# InputLevelShifter.net
KiCad netlist of a schematic drawn in Altium Designer
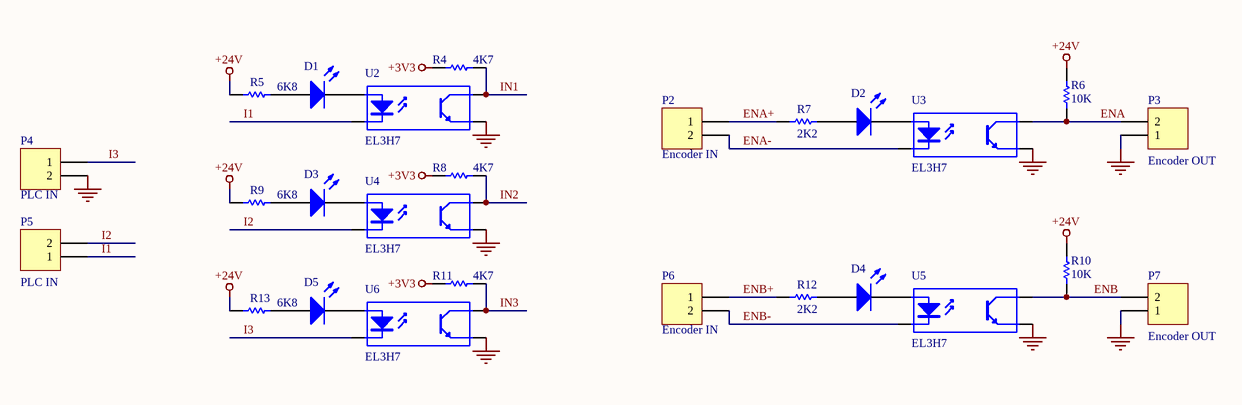
[diagram p0: InputLevelShifter.SchDoc]

(export (version "E")
  (design (tool "Eeschema 10.0.6"))
  (components
    (comp (ref "D1")
      (value "SMD0805-RED")
      (footprint "LED-0805")
      (description "Typical INFRARED GaAs LED")
      (libsource (lib "Miscellaneous Devices") (part "LED0"))
    )
    (comp (ref "D2")
      (value "SMD0805-RED")
      (footprint "LED-0805")
      (description "Typical INFRARED GaAs LED")
      (libsource (lib "Miscellaneous Devices") (part "LED0"))
    )
    (comp (ref "D3")
      (value "SMD0805-RED")
      (footprint "LED-0805")
      (description "Typical INFRARED GaAs LED")
      (libsource (lib "Miscellaneous Devices") (part "LED0"))
    )
    (comp (ref "D4")
      (value "SMD0805-RED")
      (footprint "LED-0805")
      (description "Typical INFRARED GaAs LED")
      (libsource (lib "Miscellaneous Devices") (part "LED0"))
    )
    (comp (ref "D5")
      (value "SMD0805-RED")
      (footprint "LED-0805")
      (description "Typical INFRARED GaAs LED")
      (libsource (lib "Miscellaneous Devices") (part "LED0"))
    )
    (comp (ref "P2")
      (value "Encoder IN")
      (footprint "TER-KF128-2P")
      (description "Header, 2-Pin")
      (fields (field (name "Comment") "KF128-2P"))
      (libsource (lib "") (part "Header 2_1"))
    )
    (comp (ref "P3")
      (value "Encoder OUT")
      (footprint "TER-KF128-2P")
      (description "Header, 2-Pin")
      (fields (field (name "Comment") "KF128-2P"))
      (libsource (lib "Miscellaneous Connectors") (part "Header 2"))
    )
    (comp (ref "P4")
      (value "PLC IN")
      (footprint "TER-KF128-2P")
      (description "Header, 2-Pin")
      (fields (field (name "Comment") "KF128-2P"))
      (libsource (lib "") (part "Header 2_1"))
    )
    (comp (ref "P5")
      (value "PLC IN")
      (footprint "TER-KF128-2P")
      (description "Header, 2-Pin")
      (fields (field (name "Comment") "KF128-2P"))
      (libsource (lib "") (part "Header 2_2"))
    )
    (comp (ref "P6")
      (value "Encoder IN")
      (footprint "TER-KF128-2P")
      (description "Header, 2-Pin")
      (fields (field (name "Comment") "KF128-2P"))
      (libsource (lib "") (part "Header 2_1"))
    )
    (comp (ref "P7")
      (value "Encoder OUT")
      (footprint "TER-KF128-2P")
      (description "Header, 2-Pin")
      (fields (field (name "Comment") "KF128-2P"))
      (libsource (lib "Miscellaneous Connectors") (part "Header 2"))
    )
    (comp (ref "R4")
      (value "4K7")
      (footprint "R-0805")
      (description "Resistor")
      (fields (field (name "PUBLISHER") "Altium Limited"))
      (libsource (lib "Miscellaneous Devices") (part "Res1"))
    )
    (comp (ref "R5")
      (value "6K8")
      (footprint "R-0805")
      (description "Resistor")
      (fields (field (name "PUBLISHER") "Altium Limited"))
      (libsource (lib "Miscellaneous Devices") (part "Res1"))
    )
    (comp (ref "R6")
      (value "10K")
      (footprint "R-0805")
      (description "Resistor")
      (fields (field (name "PUBLISHER") "Altium Limited"))
      (libsource (lib "Miscellaneous Devices") (part "Res1"))
    )
    (comp (ref "R7")
      (value "2K2")
      (footprint "R-0805")
      (description "Resistor")
      (fields (field (name "PUBLISHER") "Altium Limited"))
      (libsource (lib "Miscellaneous Devices") (part "Res1"))
    )
    (comp (ref "R8")
      (value "4K7")
      (footprint "R-0805")
      (description "Resistor")
      (fields (field (name "PUBLISHER") "Altium Limited"))
      (libsource (lib "Miscellaneous Devices") (part "Res1"))
    )
    (comp (ref "R9")
      (value "6K8")
      (footprint "R-0805")
      (description "Resistor")
      (fields (field (name "PUBLISHER") "Altium Limited"))
      (libsource (lib "Miscellaneous Devices") (part "Res1"))
    )
    (comp (ref "R10")
      (value "10K")
      (footprint "R-0805")
      (description "Resistor")
      (fields (field (name "PUBLISHER") "Altium Limited"))
      (libsource (lib "Miscellaneous Devices") (part "Res1"))
    )
    (comp (ref "R11")
      (value "4K7")
      (footprint "R-0805")
      (description "Resistor")
      (fields (field (name "PUBLISHER") "Altium Limited"))
      (libsource (lib "Miscellaneous Devices") (part "Res1"))
    )
    (comp (ref "R12")
      (value "2K2")
      (footprint "R-0805")
      (description "Resistor")
      (fields (field (name "PUBLISHER") "Altium Limited"))
      (libsource (lib "Miscellaneous Devices") (part "Res1"))
    )
    (comp (ref "R13")
      (value "6K8")
      (footprint "R-0805")
      (description "Resistor")
      (fields (field (name "PUBLISHER") "Altium Limited"))
      (libsource (lib "Miscellaneous Devices") (part "Res1"))
    )
    (comp (ref "U2")
      (value "EL3H7")
      (footprint "SSOP-4")
      (description "4-Pin Phototransistor Optocoupler")
      (libsource (lib "Miscellaneous Devices") (part "Optoisolator1"))
    )
    (comp (ref "U3")
      (value "EL3H7")
      (footprint "SSOP-4")
      (description "4-Pin Phototransistor Optocoupler")
      (libsource (lib "Miscellaneous Devices") (part "Optoisolator1"))
    )
    (comp (ref "U4")
      (value "EL3H7")
      (footprint "SSOP-4")
      (description "4-Pin Phototransistor Optocoupler")
      (libsource (lib "Miscellaneous Devices") (part "Optoisolator1"))
    )
    (comp (ref "U5")
      (value "EL3H7")
      (footprint "SSOP-4")
      (description "4-Pin Phototransistor Optocoupler")
      (libsource (lib "Miscellaneous Devices") (part "Optoisolator1"))
    )
    (comp (ref "U6")
      (value "EL3H7")
      (footprint "SSOP-4")
      (description "4-Pin Phototransistor Optocoupler")
      (libsource (lib "Miscellaneous Devices") (part "Optoisolator1"))
    )
  )
  (nets
    (net (code "1") (name "+3V3") (class "Default")
      (node (ref "R11") (pin "2") (pinfunction "2_2") (pintype "passive"))
      (node (ref "R4") (pin "2") (pinfunction "2_2") (pintype "passive"))
      (node (ref "R8") (pin "2") (pinfunction "2_2") (pintype "passive"))
    )
    (net (code "2") (name "+24V") (class "Default")
      (node (ref "R10") (pin "2") (pinfunction "2_2") (pintype "passive"))
      (node (ref "R13") (pin "1") (pinfunction "1_1") (pintype "passive"))
      (node (ref "R5") (pin "1") (pinfunction "1_1") (pintype "passive"))
      (node (ref "R6") (pin "2") (pinfunction "2_2") (pintype "passive"))
      (node (ref "R9") (pin "1") (pinfunction "1_1") (pintype "passive"))
    )
    (net (code "3") (name "/ENA") (class "Default")
      (node (ref "P3") (pin "2") (pinfunction "2_2") (pintype "passive"))
      (node (ref "R6") (pin "1") (pinfunction "1_1") (pintype "passive"))
      (node (ref "U3") (pin "4") (pinfunction "C_4") (pintype "passive"))
    )
    (net (code "4") (name "/ENA+") (class "Default")
      (node (ref "P2") (pin "1") (pinfunction "1_1") (pintype "passive"))
      (node (ref "R7") (pin "1") (pinfunction "1_1") (pintype "passive"))
    )
    (net (code "5") (name "/ENA-") (class "Default")
      (node (ref "P2") (pin "2") (pinfunction "2_2") (pintype "passive"))
      (node (ref "U3") (pin "2") (pinfunction "K_2") (pintype "passive"))
    )
    (net (code "6") (name "/ENB") (class "Default")
      (node (ref "P7") (pin "2") (pinfunction "2_2") (pintype "passive"))
      (node (ref "R10") (pin "1") (pinfunction "1_1") (pintype "passive"))
      (node (ref "U5") (pin "4") (pinfunction "C_4") (pintype "passive"))
    )
    (net (code "7") (name "/ENB+") (class "Default")
      (node (ref "P6") (pin "1") (pinfunction "1_1") (pintype "passive"))
      (node (ref "R12") (pin "1") (pinfunction "1_1") (pintype "passive"))
    )
    (net (code "8") (name "/ENB-") (class "Default")
      (node (ref "P6") (pin "2") (pinfunction "2_2") (pintype "passive"))
      (node (ref "U5") (pin "2") (pinfunction "K_2") (pintype "passive"))
    )
    (net (code "9") (name "/I1") (class "Default")
      (node (ref "P5") (pin "1") (pinfunction "1_1") (pintype "passive"))
      (node (ref "U2") (pin "2") (pinfunction "K_2") (pintype "passive"))
    )
    (net (code "10") (name "/I2") (class "Default")
      (node (ref "P5") (pin "2") (pinfunction "2_2") (pintype "passive"))
      (node (ref "U4") (pin "2") (pinfunction "K_2") (pintype "passive"))
    )
    (net (code "11") (name "/I3") (class "Default")
      (node (ref "P4") (pin "1") (pinfunction "1_1") (pintype "passive"))
      (node (ref "U6") (pin "2") (pinfunction "K_2") (pintype "passive"))
    )
    (net (code "12") (name "/IN1") (class "Default")
      (node (ref "R4") (pin "1") (pinfunction "1_1") (pintype "passive"))
      (node (ref "U2") (pin "4") (pinfunction "C_4") (pintype "passive"))
    )
    (net (code "13") (name "/IN2") (class "Default")
      (node (ref "R8") (pin "1") (pinfunction "1_1") (pintype "passive"))
      (node (ref "U4") (pin "4") (pinfunction "C_4") (pintype "passive"))
    )
    (net (code "14") (name "/IN3") (class "Default")
      (node (ref "R11") (pin "1") (pinfunction "1_1") (pintype "passive"))
      (node (ref "U6") (pin "4") (pinfunction "C_4") (pintype "passive"))
    )
    (net (code "15") (name "GND") (class "Default")
      (node (ref "P3") (pin "1") (pinfunction "1_1") (pintype "passive"))
      (node (ref "P4") (pin "2") (pinfunction "2_2") (pintype "passive"))
      (node (ref "P7") (pin "1") (pinfunction "1_1") (pintype "passive"))
      (node (ref "U2") (pin "3") (pinfunction "E_3") (pintype "passive"))
      (node (ref "U3") (pin "3") (pinfunction "E_3") (pintype "passive"))
      (node (ref "U4") (pin "3") (pinfunction "E_3") (pintype "passive"))
      (node (ref "U5") (pin "3") (pinfunction "E_3") (pintype "passive"))
      (node (ref "U6") (pin "3") (pinfunction "E_3") (pintype "passive"))
    )
    (net (code "16") (name "Net-(D1-A)") (class "Default")
      (node (ref "D1") (pin "1") (pinfunction "A_1") (pintype "passive"))
      (node (ref "R5") (pin "2") (pinfunction "2_2") (pintype "passive"))
    )
    (net (code "17") (name "Net-(D1-K)") (class "Default")
      (node (ref "D1") (pin "2") (pinfunction "K_2") (pintype "passive"))
      (node (ref "U2") (pin "1") (pinfunction "A_1") (pintype "passive"))
    )
    (net (code "18") (name "Net-(D2-A)") (class "Default")
      (node (ref "D2") (pin "1") (pinfunction "A_1") (pintype "passive"))
      (node (ref "R7") (pin "2") (pinfunction "2_2") (pintype "passive"))
    )
    (net (code "19") (name "Net-(D2-K)") (class "Default")
      (node (ref "D2") (pin "2") (pinfunction "K_2") (pintype "passive"))
      (node (ref "U3") (pin "1") (pinfunction "A_1") (pintype "passive"))
    )
    (net (code "20") (name "Net-(D3-A)") (class "Default")
      (node (ref "D3") (pin "1") (pinfunction "A_1") (pintype "passive"))
      (node (ref "R9") (pin "2") (pinfunction "2_2") (pintype "passive"))
    )
    (net (code "21") (name "Net-(D3-K)") (class "Default")
      (node (ref "D3") (pin "2") (pinfunction "K_2") (pintype "passive"))
      (node (ref "U4") (pin "1") (pinfunction "A_1") (pintype "passive"))
    )
    (net (code "22") (name "Net-(D4-A)") (class "Default")
      (node (ref "D4") (pin "1") (pinfunction "A_1") (pintype "passive"))
      (node (ref "R12") (pin "2") (pinfunction "2_2") (pintype "passive"))
    )
    (net (code "23") (name "Net-(D4-K)") (class "Default")
      (node (ref "D4") (pin "2") (pinfunction "K_2") (pintype "passive"))
      (node (ref "U5") (pin "1") (pinfunction "A_1") (pintype "passive"))
    )
    (net (code "24") (name "Net-(D5-A)") (class "Default")
      (node (ref "D5") (pin "1") (pinfunction "A_1") (pintype "passive"))
      (node (ref "R13") (pin "2") (pinfunction "2_2") (pintype "passive"))
    )
    (net (code "25") (name "Net-(D5-K)") (class "Default")
      (node (ref "D5") (pin "2") (pinfunction "K_2") (pintype "passive"))
      (node (ref "U6") (pin "1") (pinfunction "A_1") (pintype "passive"))
    )
  )
)
